# M_D_ext_power-solar1.net
KiCad netlist of a schematic drawn in EAGLE
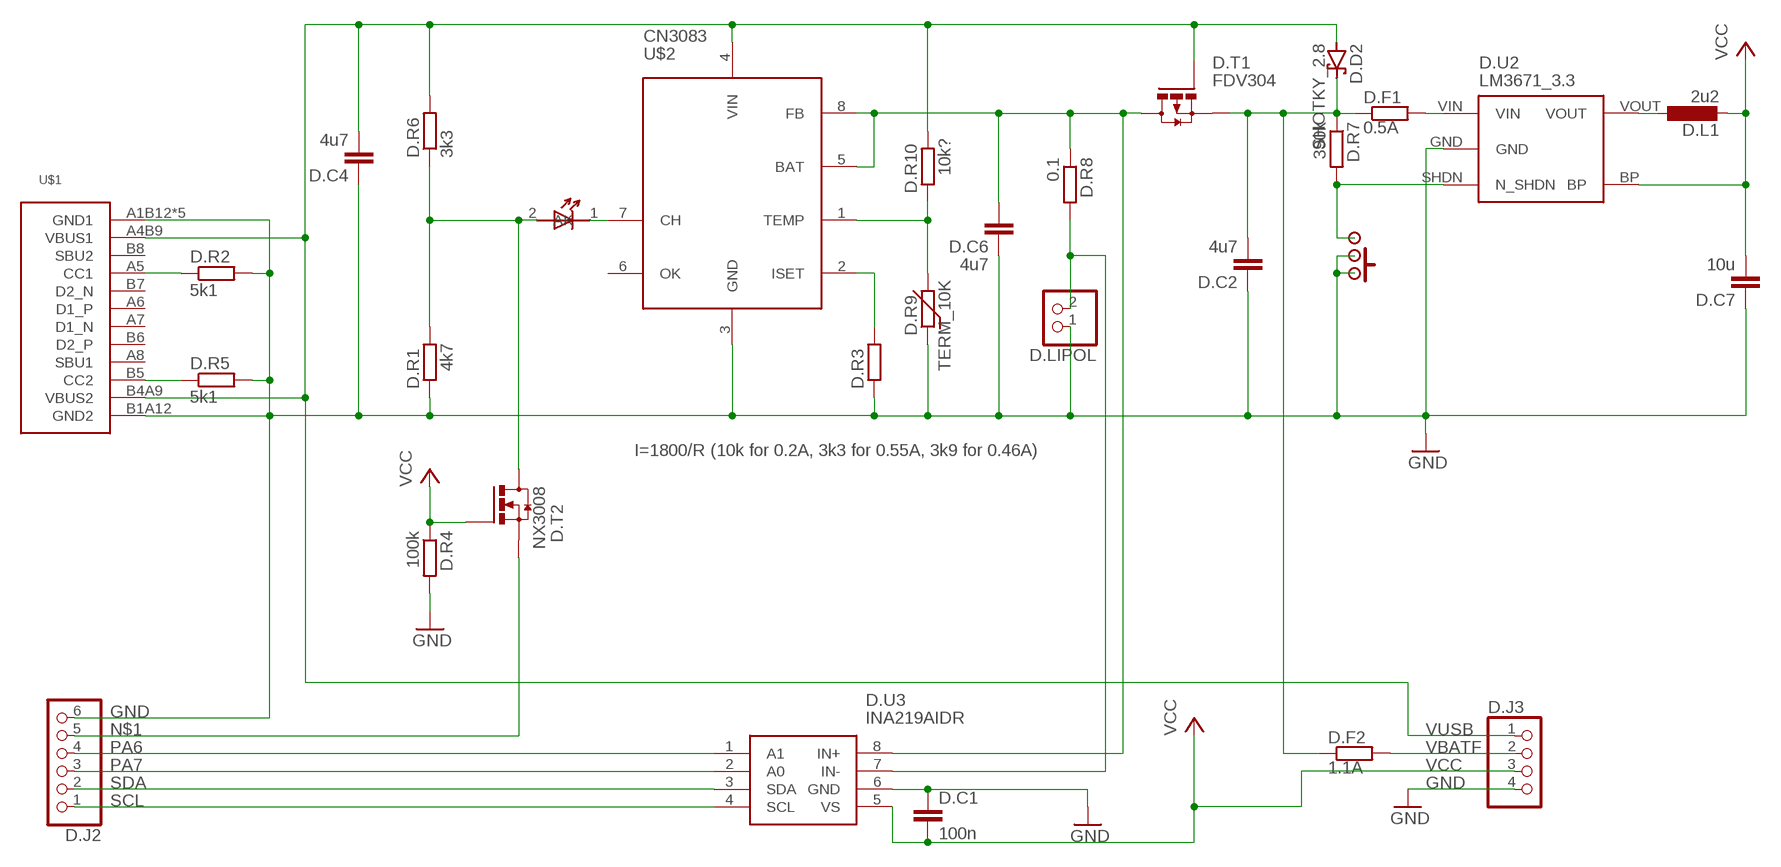
[diagram p0: schematic, sheet 1]

(export (version "E")
  (design (tool "Eeschema 10.0.6"))
  (components
    (comp (ref "D.C1")
      (value "100n")
      (footprint "eagle-import:C0603")
      (libsource (lib "eagle-import") (part "C-EUC0603"))
    )
    (comp (ref "D.C2")
      (value "4u7")
      (footprint "eagle-import:C0603")
      (libsource (lib "eagle-import") (part "C-EUC0603"))
    )
    (comp (ref "D.C4")
      (value "4u7")
      (footprint "eagle-import:C0603")
      (libsource (lib "eagle-import") (part "C-EUC0603"))
    )
    (comp (ref "D.C6")
      (value "4u7")
      (footprint "eagle-import:C0603")
      (libsource (lib "eagle-import") (part "C-EUC0603"))
    )
    (comp (ref "D.C7")
      (value "10u")
      (footprint "eagle-import:C0805")
      (libsource (lib "eagle-import") (part "C-EUC0805"))
    )
    (comp (ref "D.D1")
      (value "LED_1.8")
      (footprint "eagle-import:LED_1.8")
      (libsource (lib "eagle-import") (part "LED_1.8"))
    )
    (comp (ref "D.D2")
      (value "SHOTKY_2.8")
      (footprint "eagle-import:SHOTKY_2.8")
      (libsource (lib "eagle-import") (part "SHOTKY_2.8"))
    )
    (comp (ref "D.F1")
      (value "0.5A")
      (footprint "eagle-import:R0805")
      (libsource (lib "eagle-import") (part "R-EU_R0805"))
    )
    (comp (ref "D.F2")
      (value "1.1A")
      (footprint "eagle-import:R0805")
      (libsource (lib "eagle-import") (part "R-EU_R0805"))
    )
    (comp (ref "D.J2")
      (value "PINHD-1X6")
      (footprint "eagle-import:1X06")
      (libsource (lib "eagle-import") (part "PINHD-1X6"))
    )
    (comp (ref "D.J3")
      (value "PINHD-1X4")
      (footprint "eagle-import:1X04")
      (libsource (lib "eagle-import") (part "PINHD-1X4"))
    )
    (comp (ref "D.L1")
      (value "2u2")
      (footprint "eagle-import:L3230M")
      (libsource (lib "eagle-import") (part "L-EUL3230M"))
    )
    (comp (ref "D.LIPOL")
      (value "PINHD-1X2")
      (footprint "eagle-import:1X02")
      (libsource (lib "eagle-import") (part "PINHD-1X2"))
    )
    (comp (ref "D.ON/OFF/RESET")
      (value "SWITCH")
      (footprint "eagle-import:SWITCH")
      (libsource (lib "eagle-import") (part "SWITCH"))
    )
    (comp (ref "D.R1")
      (value "4k7")
      (footprint "eagle-import:R0603")
      (libsource (lib "eagle-import") (part "R-EU_R0603"))
    )
    (comp (ref "D.R2")
      (value "5k1")
      (footprint "eagle-import:R0603")
      (libsource (lib "eagle-import") (part "R-EU_R0603"))
    )
    (comp (ref "D.R3")
      (value "I=1800/R (10k for 0.2A, 3k3 for 0.55A, 3k9 for 0.46A)")
      (footprint "eagle-import:R0603")
      (libsource (lib "eagle-import") (part "R-EU_R0603"))
    )
    (comp (ref "D.R4")
      (value "100k")
      (footprint "eagle-import:R0603")
      (libsource (lib "eagle-import") (part "R-EU_R0603"))
    )
    (comp (ref "D.R5")
      (value "5k1")
      (footprint "eagle-import:R0603")
      (libsource (lib "eagle-import") (part "R-EU_R0603"))
    )
    (comp (ref "D.R6")
      (value "3k3")
      (footprint "eagle-import:R0603")
      (libsource (lib "eagle-import") (part "R-EU_R0603"))
    )
    (comp (ref "D.R7")
      (value "390k")
      (footprint "eagle-import:R0603")
      (libsource (lib "eagle-import") (part "R-EU_R0603"))
    )
    (comp (ref "D.R8")
      (value "0.1")
      (footprint "eagle-import:R0805")
      (libsource (lib "eagle-import") (part "R-EU_R0805"))
    )
    (comp (ref "D.R9")
      (value "TERM_10K")
      (footprint "eagle-import:THERM")
      (libsource (lib "eagle-import") (part "THERM"))
    )
    (comp (ref "D.R10")
      (value "10k?")
      (footprint "eagle-import:R0603")
      (libsource (lib "eagle-import") (part "R-EU_R0603"))
    )
    (comp (ref "D.T1")
      (value "FDV304")
      (footprint "eagle-import:SO23")
      (libsource (lib "eagle-import") (part "P-MOSFET"))
    )
    (comp (ref "D.T2")
      (value "NX3008")
      (footprint "eagle-import:SO23")
      (libsource (lib "eagle-import") (part "N-MOSFET"))
    )
    (comp (ref "D.U2")
      (value "LM3671_3.3")
      (footprint "eagle-import:SOT32-5")
      (libsource (lib "eagle-import") (part "STABILISER_APE8865"))
    )
    (comp (ref "D.U3")
      (value "INA219AIDR")
      (footprint "eagle-import:SOIC127P600X175-8N")
      (fields (field (name "MOUSER_PART_NUMBER") "595-INA219AIDR"))
      (libsource (lib "eagle-import") (part "INA219AIDR"))
    )
    (comp (ref "U$1")
      (value "USB-C")
      (footprint "eagle-import:USB-C")
      (libsource (lib "eagle-import") (part "USB-C"))
    )
    (comp (ref "U$2")
      (value "CN3083")
      (footprint "eagle-import:SOP8")
      (libsource (lib "eagle-import") (part "CN3083"))
    )
  )
  (nets
    (net (code "1") (name "/N$1") (class "Default")
      (node (ref "D.J2") (pin "5") (pinfunction "5_5") (pintype "passive"))
      (node (ref "D.T2") (pin "S") (pinfunction "S_S") (pintype "passive"))
    )
    (net (code "2") (name "/PA6") (class "Default")
      (node (ref "D.J2") (pin "4") (pinfunction "4_4") (pintype "passive"))
      (node (ref "D.U3") (pin "1") (pinfunction "A1_1") (pintype "bidirectional"))
    )
    (net (code "3") (name "/PA7") (class "Default")
      (node (ref "D.J2") (pin "3") (pinfunction "3_3") (pintype "passive"))
      (node (ref "D.U3") (pin "2") (pinfunction "A0_2") (pintype "bidirectional"))
    )
    (net (code "4") (name "/SCL") (class "Default")
      (node (ref "D.J2") (pin "1") (pinfunction "1_1") (pintype "passive"))
      (node (ref "D.U3") (pin "4") (pinfunction "SCL_4") (pintype "bidirectional"))
    )
    (net (code "5") (name "/SDA") (class "Default")
      (node (ref "D.J2") (pin "2") (pinfunction "2_2") (pintype "passive"))
      (node (ref "D.U3") (pin "3") (pinfunction "SDA_3") (pintype "bidirectional"))
    )
    (net (code "6") (name "/VBATF") (class "Default")
      (node (ref "D.F2") (pin "2") (pinfunction "2_2") (pintype "passive"))
      (node (ref "D.J3") (pin "2") (pinfunction "2_2") (pintype "passive"))
    )
    (net (code "7") (name "/VUSB") (class "Default")
      (node (ref "D.C4") (pin "2") (pinfunction "2_2") (pintype "passive"))
      (node (ref "D.D2") (pin "A") (pinfunction "A_A") (pintype "passive"))
      (node (ref "D.J3") (pin "1") (pinfunction "1_1") (pintype "passive"))
      (node (ref "D.R10") (pin "2") (pinfunction "2_2") (pintype "passive"))
      (node (ref "D.R6") (pin "2") (pinfunction "2_2") (pintype "passive"))
      (node (ref "D.T1") (pin "G") (pinfunction "G_G") (pintype "passive"))
      (node (ref "U$1") (pin "A4B9") (pinfunction "VBUS1_A4B9") (pintype "bidirectional"))
      (node (ref "U$1") (pin "B4A9") (pinfunction "VBUS2_B4A9") (pintype "bidirectional"))
      (node (ref "U$2") (pin "4") (pinfunction "VIN_4") (pintype "bidirectional"))
    )
    (net (code "8") (name "GND") (class "Default")
      (node (ref "D.C1") (pin "1") (pinfunction "1_1") (pintype "passive"))
      (node (ref "D.C2") (pin "1") (pinfunction "1_1") (pintype "passive"))
      (node (ref "D.C4") (pin "1") (pinfunction "1_1") (pintype "passive"))
      (node (ref "D.C6") (pin "1") (pinfunction "1_1") (pintype "passive"))
      (node (ref "D.C7") (pin "1") (pinfunction "1_1") (pintype "passive"))
      (node (ref "D.J2") (pin "6") (pinfunction "6_6") (pintype "passive"))
      (node (ref "D.J3") (pin "4") (pinfunction "4_4") (pintype "passive"))
      (node (ref "D.LIPOL") (pin "1") (pinfunction "1_1") (pintype "passive"))
      (node (ref "D.ON/OFF/RESET") (pin "P$1") (pinfunction "P$1_P$1") (pintype "bidirectional"))
      (node (ref "D.ON/OFF/RESET") (pin "P$2") (pinfunction "P$2_P$2") (pintype "bidirectional"))
      (node (ref "D.ON/OFF/RESET") (pin "P$4") (pinfunction "P$1_P$4") (pintype "bidirectional"))
      (node (ref "D.R1") (pin "1") (pinfunction "1_1") (pintype "passive"))
      (node (ref "D.R2") (pin "2") (pinfunction "2_2") (pintype "passive"))
      (node (ref "D.R3") (pin "1") (pinfunction "1_1") (pintype "passive"))
      (node (ref "D.R4") (pin "2") (pinfunction "2_2") (pintype "passive"))
      (node (ref "D.R5") (pin "2") (pinfunction "2_2") (pintype "passive"))
      (node (ref "D.R9") (pin "1") (pinfunction "1_1") (pintype "passive"))
      (node (ref "D.U2") (pin "GND") (pinfunction "GND_GND") (pintype "bidirectional"))
      (node (ref "D.U3") (pin "6") (pinfunction "GND_6") (pintype "bidirectional"))
      (node (ref "U$1") (pin "A1B12") (pinfunction "GND1_A1B12") (pintype "bidirectional"))
      (node (ref "U$1") (pin "B1A12") (pinfunction "GND2_B1A12") (pintype "bidirectional"))
      (node (ref "U$1") (pin "SH1") (pinfunction "GND1_SH1") (pintype "bidirectional"))
      (node (ref "U$1") (pin "SH2") (pinfunction "GND1_SH2") (pintype "bidirectional"))
      (node (ref "U$1") (pin "SH3") (pinfunction "GND1_SH3") (pintype "bidirectional"))
      (node (ref "U$1") (pin "SH4") (pinfunction "GND1_SH4") (pintype "bidirectional"))
      (node (ref "U$2") (pin "3") (pinfunction "GND_3") (pintype "bidirectional"))
    )
    (net (code "9") (name "Net-(D.D1-A)") (class "Default")
      (node (ref "D.D1") (pin "2") (pinfunction "A_2") (pintype "bidirectional"))
      (node (ref "D.R1") (pin "2") (pinfunction "2_2") (pintype "passive"))
      (node (ref "D.R6") (pin "1") (pinfunction "1_1") (pintype "passive"))
      (node (ref "D.T2") (pin "D") (pinfunction "D_D") (pintype "passive"))
    )
    (net (code "10") (name "Net-(D.D1-K)") (class "Default")
      (node (ref "D.D1") (pin "1") (pinfunction "K_1") (pintype "bidirectional"))
      (node (ref "U$2") (pin "7") (pinfunction "CH_7") (pintype "bidirectional"))
    )
    (net (code "11") (name "Net-(D.D2-C)") (class "Default")
      (node (ref "D.C2") (pin "2") (pinfunction "2_2") (pintype "passive"))
      (node (ref "D.D2") (pin "K") (pinfunction "C_K") (pintype "passive"))
      (node (ref "D.F1") (pin "1") (pinfunction "1_1") (pintype "passive"))
      (node (ref "D.F2") (pin "1") (pinfunction "1_1") (pintype "passive"))
      (node (ref "D.R7") (pin "1") (pinfunction "1_1") (pintype "passive"))
      (node (ref "D.T1") (pin "S") (pinfunction "S_S") (pintype "passive"))
    )
    (net (code "12") (name "Net-(D.F1-Pad2)") (class "Default")
      (node (ref "D.F1") (pin "2") (pinfunction "2_2") (pintype "passive"))
      (node (ref "D.U2") (pin "VIN") (pinfunction "VIN_VIN") (pintype "bidirectional"))
    )
    (net (code "13") (name "Net-(D.L1-Pad1)") (class "Default")
      (node (ref "D.L1") (pin "1") (pinfunction "1_1") (pintype "passive"))
      (node (ref "D.U2") (pin "VOUT") (pinfunction "VOUT_VOUT") (pintype "bidirectional"))
    )
    (net (code "14") (name "Net-(D.U2-N_SHDN)") (class "Default")
      (node (ref "D.ON/OFF/RESET") (pin "P$3") (pinfunction "P$3_P$3") (pintype "bidirectional"))
      (node (ref "D.ON/OFF/RESET") (pin "P$5") (pinfunction "P$3_P$5") (pintype "bidirectional"))
      (node (ref "D.R7") (pin "2") (pinfunction "2_2") (pintype "passive"))
      (node (ref "D.U2") (pin "SHDN") (pinfunction "N_SHDN_SHDN") (pintype "bidirectional"))
    )
    (net (code "15") (name "Net-(D.U3-IN+)") (class "Default")
      (node (ref "D.C6") (pin "2") (pinfunction "2_2") (pintype "passive"))
      (node (ref "D.R8") (pin "1") (pinfunction "1_1") (pintype "passive"))
      (node (ref "D.T1") (pin "D") (pinfunction "D_D") (pintype "passive"))
      (node (ref "D.U3") (pin "8") (pinfunction "IN+_8") (pintype "bidirectional"))
      (node (ref "U$2") (pin "5") (pinfunction "BAT_5") (pintype "bidirectional"))
      (node (ref "U$2") (pin "8") (pinfunction "FB_8") (pintype "bidirectional"))
    )
    (net (code "16") (name "Net-(D.U3-IN-)") (class "Default")
      (node (ref "D.LIPOL") (pin "2") (pinfunction "2_2") (pintype "passive"))
      (node (ref "D.R8") (pin "2") (pinfunction "2_2") (pintype "passive"))
      (node (ref "D.U3") (pin "7") (pinfunction "IN-_7") (pintype "bidirectional"))
    )
    (net (code "17") (name "Net-(U$1-CC1)") (class "Default")
      (node (ref "D.R2") (pin "1") (pinfunction "1_1") (pintype "passive"))
      (node (ref "U$1") (pin "A5") (pinfunction "CC1_A5") (pintype "bidirectional"))
    )
    (net (code "18") (name "Net-(U$1-CC2)") (class "Default")
      (node (ref "D.R5") (pin "1") (pinfunction "1_1") (pintype "passive"))
      (node (ref "U$1") (pin "B5") (pinfunction "CC2_B5") (pintype "bidirectional"))
    )
    (net (code "19") (name "Net-(U$2-ISET)") (class "Default")
      (node (ref "D.R3") (pin "2") (pinfunction "2_2") (pintype "passive"))
      (node (ref "U$2") (pin "2") (pinfunction "ISET_2") (pintype "bidirectional"))
    )
    (net (code "20") (name "Net-(U$2-TEMP)") (class "Default")
      (node (ref "D.R10") (pin "1") (pinfunction "1_1") (pintype "passive"))
      (node (ref "D.R9") (pin "2") (pinfunction "2_2") (pintype "passive"))
      (node (ref "U$2") (pin "1") (pinfunction "TEMP_1") (pintype "bidirectional"))
    )
    (net (code "21") (name "VCC") (class "Default")
      (node (ref "D.C1") (pin "2") (pinfunction "2_2") (pintype "passive"))
      (node (ref "D.C7") (pin "2") (pinfunction "2_2") (pintype "passive"))
      (node (ref "D.J3") (pin "3") (pinfunction "3_3") (pintype "passive"))
      (node (ref "D.L1") (pin "2") (pinfunction "2_2") (pintype "passive"))
      (node (ref "D.R4") (pin "1") (pinfunction "1_1") (pintype "passive"))
      (node (ref "D.T2") (pin "G") (pinfunction "G_G") (pintype "passive"))
      (node (ref "D.U2") (pin "BP") (pinfunction "BP_BP") (pintype "bidirectional"))
      (node (ref "D.U3") (pin "5") (pinfunction "VS_5") (pintype "bidirectional"))
    )
    (net (code "22") (name "unconnected-(U$1-D1_N-PadA7)") (class "Default")
      (node (ref "U$1") (pin "A7") (pinfunction "D1_N_A7") (pintype "bidirectional"))
    )
    (net (code "23") (name "unconnected-(U$1-D1_P-PadA6)") (class "Default")
      (node (ref "U$1") (pin "A6") (pinfunction "D1_P_A6") (pintype "bidirectional"))
    )
    (net (code "24") (name "unconnected-(U$1-D2_N-PadB7)") (class "Default")
      (node (ref "U$1") (pin "B7") (pinfunction "D2_N_B7") (pintype "bidirectional"))
    )
    (net (code "25") (name "unconnected-(U$1-D2_P-PadB6)") (class "Default")
      (node (ref "U$1") (pin "B6") (pinfunction "D2_P_B6") (pintype "bidirectional"))
    )
    (net (code "26") (name "unconnected-(U$1-SBU1-PadA8)") (class "Default")
      (node (ref "U$1") (pin "A8") (pinfunction "SBU1_A8") (pintype "bidirectional"))
    )
    (net (code "27") (name "unconnected-(U$1-SBU2-PadB8)") (class "Default")
      (node (ref "U$1") (pin "B8") (pinfunction "SBU2_B8") (pintype "bidirectional"))
    )
    (net (code "28") (name "unconnected-(U$2-OK-Pad6)") (class "Default")
      (node (ref "U$2") (pin "6") (pinfunction "OK_6") (pintype "bidirectional"))
    )
  )
)
